# LightsPCB.net
KiCad netlist of a schematic drawn in EAGLE
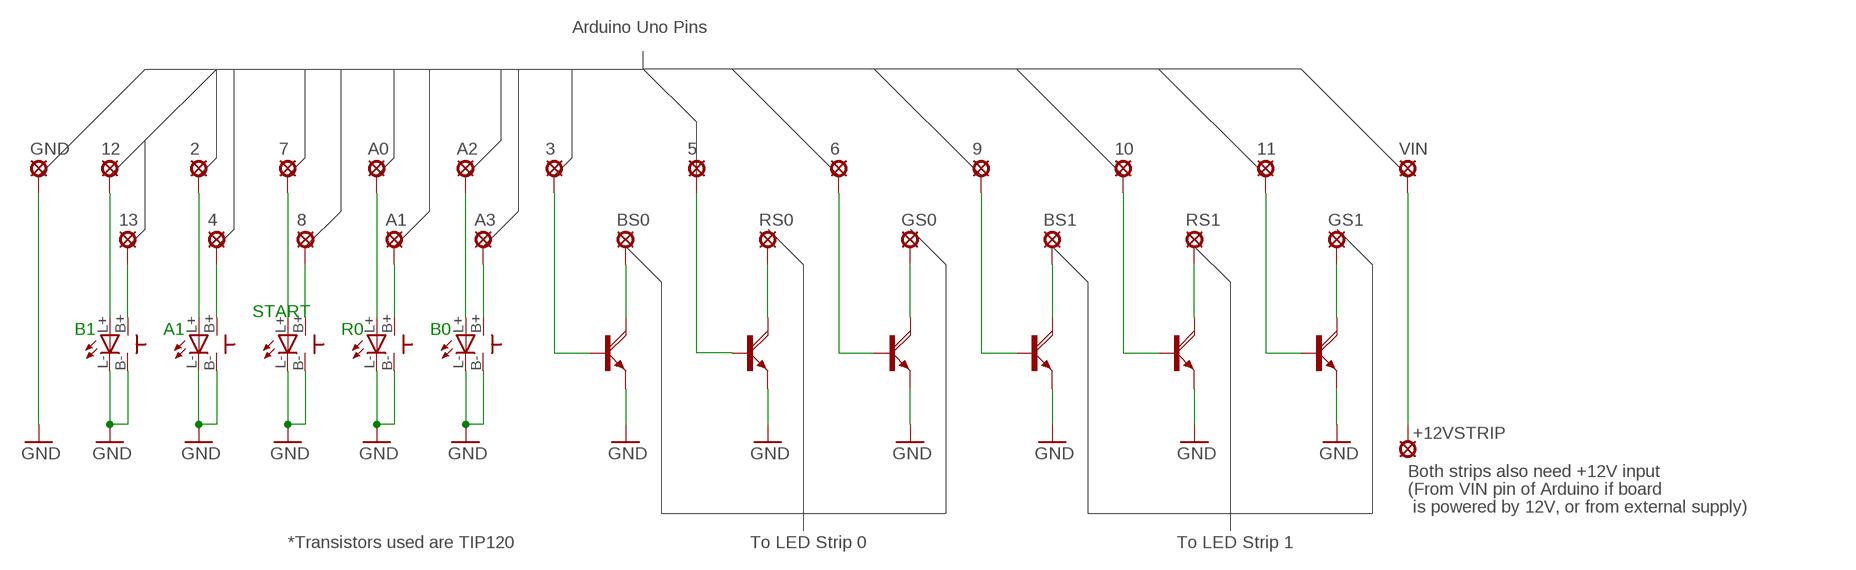
[diagram p0: schematic, sheet 1]

(export (version "E")
  (design (tool "Eeschema 10.0.6"))
  (components
    (comp (ref "+12VSTRIP")
      (value "LSP10")
      (footprint "eagle-import:LSP10")
      (libsource (lib "eagle-import") (part "LSP10"))
    )
    (comp (ref "2")
      (value "LSP10")
      (footprint "eagle-import:LSP10")
      (libsource (lib "eagle-import") (part "LSP10"))
    )
    (comp (ref "3")
      (value "LSP10")
      (footprint "eagle-import:LSP10")
      (libsource (lib "eagle-import") (part "LSP10"))
    )
    (comp (ref "4")
      (value "LSP10")
      (footprint "eagle-import:LSP10")
      (libsource (lib "eagle-import") (part "LSP10"))
    )
    (comp (ref "5")
      (value "LSP10")
      (footprint "eagle-import:LSP10")
      (libsource (lib "eagle-import") (part "LSP10"))
    )
    (comp (ref "6")
      (value "LSP10")
      (footprint "eagle-import:LSP10")
      (libsource (lib "eagle-import") (part "LSP10"))
    )
    (comp (ref "7")
      (value "LSP10")
      (footprint "eagle-import:LSP10")
      (libsource (lib "eagle-import") (part "LSP10"))
    )
    (comp (ref "8")
      (value "LSP10")
      (footprint "eagle-import:LSP10")
      (libsource (lib "eagle-import") (part "LSP10"))
    )
    (comp (ref "9")
      (value "LSP10")
      (footprint "eagle-import:LSP10")
      (libsource (lib "eagle-import") (part "LSP10"))
    )
    (comp (ref "10")
      (value "LSP10")
      (footprint "eagle-import:LSP10")
      (libsource (lib "eagle-import") (part "LSP10"))
    )
    (comp (ref "11")
      (value "LSP10")
      (footprint "eagle-import:LSP10")
      (libsource (lib "eagle-import") (part "LSP10"))
    )
    (comp (ref "12")
      (value "LSP10")
      (footprint "eagle-import:LSP10")
      (libsource (lib "eagle-import") (part "LSP10"))
    )
    (comp (ref "13")
      (value "LSP10")
      (footprint "eagle-import:LSP10")
      (libsource (lib "eagle-import") (part "LSP10"))
    )
    (comp (ref "A0")
      (value "LSP10")
      (footprint "eagle-import:LSP10")
      (libsource (lib "eagle-import") (part "LSP10"))
    )
    (comp (ref "A1")
      (value "LSP10")
      (footprint "eagle-import:LSP10")
      (libsource (lib "eagle-import") (part "LSP10"))
    )
    (comp (ref "A2")
      (value "LSP10")
      (footprint "eagle-import:LSP10")
      (libsource (lib "eagle-import") (part "LSP10"))
    )
    (comp (ref "A3")
      (value "LSP10")
      (footprint "eagle-import:LSP10")
      (libsource (lib "eagle-import") (part "LSP10"))
    )
    (comp (ref "B0")
      (value "LEDBUTTON")
      (footprint "eagle-import:LEDBUTTON")
      (libsource (lib "eagle-import") (part "LEDBUTTON"))
    )
    (comp (ref "B1")
      (value "LEDBUTTON")
      (footprint "eagle-import:LEDBUTTON")
      (libsource (lib "eagle-import") (part "LEDBUTTON"))
    )
    (comp (ref "BS0")
      (value "LSP10")
      (footprint "eagle-import:LSP10")
      (libsource (lib "eagle-import") (part "LSP10"))
    )
    (comp (ref "BS1")
      (value "LSP10")
      (footprint "eagle-import:LSP10")
      (libsource (lib "eagle-import") (part "LSP10"))
    )
    (comp (ref "GND")
      (value "LSP10")
      (footprint "eagle-import:LSP10")
      (libsource (lib "eagle-import") (part "LSP10"))
    )
    (comp (ref "GS0")
      (value "LSP10")
      (footprint "eagle-import:LSP10")
      (libsource (lib "eagle-import") (part "LSP10"))
    )
    (comp (ref "GS1")
      (value "LSP10")
      (footprint "eagle-import:LSP10")
      (libsource (lib "eagle-import") (part "LSP10"))
    )
    (comp (ref "R0")
      (value "LEDBUTTON")
      (footprint "eagle-import:LEDBUTTON")
      (libsource (lib "eagle-import") (part "LEDBUTTON"))
    )
    (comp (ref "R1")
      (value "LEDBUTTON")
      (footprint "eagle-import:LEDBUTTON")
      (libsource (lib "eagle-import") (part "LEDBUTTON"))
    )
    (comp (ref "RS0")
      (value "LSP10")
      (footprint "eagle-import:LSP10")
      (libsource (lib "eagle-import") (part "LSP10"))
    )
    (comp (ref "RS1")
      (value "LSP10")
      (footprint "eagle-import:LSP10")
      (libsource (lib "eagle-import") (part "LSP10"))
    )
    (comp (ref "START")
      (value "LEDBUTTON")
      (footprint "eagle-import:LEDBUTTON")
      (libsource (lib "eagle-import") (part "LEDBUTTON"))
    )
    (comp (ref "U1")
      (value "TIP120")
      (footprint "eagle-import:TO220AH")
      (libsource (lib "eagle-import") (part "TIP120"))
    )
    (comp (ref "U2")
      (value "TIP120")
      (footprint "eagle-import:TO220AH")
      (libsource (lib "eagle-import") (part "TIP120"))
    )
    (comp (ref "U3")
      (value "TIP120")
      (footprint "eagle-import:TO220AH")
      (libsource (lib "eagle-import") (part "TIP120"))
    )
    (comp (ref "U4")
      (value "TIP120")
      (footprint "eagle-import:TO220AH")
      (libsource (lib "eagle-import") (part "TIP120"))
    )
    (comp (ref "U5")
      (value "TIP120")
      (footprint "eagle-import:TO220AH")
      (libsource (lib "eagle-import") (part "TIP120"))
    )
    (comp (ref "U6")
      (value "TIP120")
      (footprint "eagle-import:TO220AH")
      (libsource (lib "eagle-import") (part "TIP120"))
    )
    (comp (ref "VIN")
      (value "LSP10")
      (footprint "eagle-import:LSP10")
      (libsource (lib "eagle-import") (part "LSP10"))
    )
  )
  (nets
    (net (code "1") (name "GND") (class "Default")
      (node (ref "B0") (pin "B-") (pinfunction "B-_B-") (pintype "bidirectional"))
      (node (ref "B0") (pin "L-") (pinfunction "L-_L-") (pintype "bidirectional"))
      (node (ref "B1") (pin "B-") (pinfunction "B-_B-") (pintype "bidirectional"))
      (node (ref "B1") (pin "L-") (pinfunction "L-_L-") (pintype "bidirectional"))
      (node (ref "GND") (pin "MP") (pinfunction "MP_MP") (pintype "passive"))
      (node (ref "R0") (pin "B-") (pinfunction "B-_B-") (pintype "bidirectional"))
      (node (ref "R0") (pin "L-") (pinfunction "L-_L-") (pintype "bidirectional"))
      (node (ref "R1") (pin "B-") (pinfunction "B-_B-") (pintype "bidirectional"))
      (node (ref "R1") (pin "L-") (pinfunction "L-_L-") (pintype "bidirectional"))
      (node (ref "START") (pin "B-") (pinfunction "B-_B-") (pintype "bidirectional"))
      (node (ref "START") (pin "L-") (pinfunction "L-_L-") (pintype "bidirectional"))
      (node (ref "U1") (pin "E") (pinfunction "E_E") (pintype "passive"))
      (node (ref "U2") (pin "E") (pinfunction "E_E") (pintype "passive"))
      (node (ref "U3") (pin "E") (pinfunction "E_E") (pintype "passive"))
      (node (ref "U4") (pin "E") (pinfunction "E_E") (pintype "passive"))
      (node (ref "U5") (pin "E") (pinfunction "E_E") (pintype "passive"))
      (node (ref "U6") (pin "E") (pinfunction "E_E") (pintype "passive"))
    )
    (net (code "2") (name "Net-(+12VSTRIP-PadMP)") (class "Default")
      (node (ref "+12VSTRIP") (pin "MP") (pinfunction "MP_MP") (pintype "passive"))
      (node (ref "VIN") (pin "MP") (pinfunction "MP_MP") (pintype "passive"))
    )
    (net (code "3") (name "Net-(2-PadMP)") (class "Default")
      (node (ref "2") (pin "MP") (pinfunction "MP_MP") (pintype "passive"))
      (node (ref "R1") (pin "L+") (pinfunction "L+_L+") (pintype "bidirectional"))
    )
    (net (code "4") (name "Net-(3-PadMP)") (class "Default")
      (node (ref "3") (pin "MP") (pinfunction "MP_MP") (pintype "passive"))
      (node (ref "U1") (pin "B") (pinfunction "B_B") (pintype "passive"))
    )
    (net (code "5") (name "Net-(4-PadMP)") (class "Default")
      (node (ref "4") (pin "MP") (pinfunction "MP_MP") (pintype "passive"))
      (node (ref "R1") (pin "B+") (pinfunction "B+_B+") (pintype "bidirectional"))
    )
    (net (code "6") (name "Net-(5-PadMP)") (class "Default")
      (node (ref "5") (pin "MP") (pinfunction "MP_MP") (pintype "passive"))
      (node (ref "U2") (pin "B") (pinfunction "B_B") (pintype "passive"))
    )
    (net (code "7") (name "Net-(6-PadMP)") (class "Default")
      (node (ref "6") (pin "MP") (pinfunction "MP_MP") (pintype "passive"))
      (node (ref "U3") (pin "B") (pinfunction "B_B") (pintype "passive"))
    )
    (net (code "8") (name "Net-(7-PadMP)") (class "Default")
      (node (ref "7") (pin "MP") (pinfunction "MP_MP") (pintype "passive"))
      (node (ref "START") (pin "L+") (pinfunction "L+_L+") (pintype "bidirectional"))
    )
    (net (code "9") (name "Net-(8-PadMP)") (class "Default")
      (node (ref "8") (pin "MP") (pinfunction "MP_MP") (pintype "passive"))
      (node (ref "START") (pin "B+") (pinfunction "B+_B+") (pintype "bidirectional"))
    )
    (net (code "10") (name "Net-(9-PadMP)") (class "Default")
      (node (ref "9") (pin "MP") (pinfunction "MP_MP") (pintype "passive"))
      (node (ref "U5") (pin "B") (pinfunction "B_B") (pintype "passive"))
    )
    (net (code "11") (name "Net-(10-PadMP)") (class "Default")
      (node (ref "10") (pin "MP") (pinfunction "MP_MP") (pintype "passive"))
      (node (ref "U4") (pin "B") (pinfunction "B_B") (pintype "passive"))
    )
    (net (code "12") (name "Net-(11-PadMP)") (class "Default")
      (node (ref "11") (pin "MP") (pinfunction "MP_MP") (pintype "passive"))
      (node (ref "U6") (pin "B") (pinfunction "B_B") (pintype "passive"))
    )
    (net (code "13") (name "Net-(12-PadMP)") (class "Default")
      (node (ref "12") (pin "MP") (pinfunction "MP_MP") (pintype "passive"))
      (node (ref "B1") (pin "L+") (pinfunction "L+_L+") (pintype "bidirectional"))
    )
    (net (code "14") (name "Net-(13-PadMP)") (class "Default")
      (node (ref "13") (pin "MP") (pinfunction "MP_MP") (pintype "passive"))
      (node (ref "B1") (pin "B+") (pinfunction "B+_B+") (pintype "bidirectional"))
    )
    (net (code "15") (name "Net-(A0-PadMP)") (class "Default")
      (node (ref "A0") (pin "MP") (pinfunction "MP_MP") (pintype "passive"))
      (node (ref "R0") (pin "L+") (pinfunction "L+_L+") (pintype "bidirectional"))
    )
    (net (code "16") (name "Net-(A1-PadMP)") (class "Default")
      (node (ref "A1") (pin "MP") (pinfunction "MP_MP") (pintype "passive"))
      (node (ref "R0") (pin "B+") (pinfunction "B+_B+") (pintype "bidirectional"))
    )
    (net (code "17") (name "Net-(A2-PadMP)") (class "Default")
      (node (ref "A2") (pin "MP") (pinfunction "MP_MP") (pintype "passive"))
      (node (ref "B0") (pin "L+") (pinfunction "L+_L+") (pintype "bidirectional"))
    )
    (net (code "18") (name "Net-(A3-PadMP)") (class "Default")
      (node (ref "A3") (pin "MP") (pinfunction "MP_MP") (pintype "passive"))
      (node (ref "B0") (pin "B+") (pinfunction "B+_B+") (pintype "bidirectional"))
    )
    (net (code "19") (name "Net-(BS0-PadMP)") (class "Default")
      (node (ref "BS0") (pin "MP") (pinfunction "MP_MP") (pintype "passive"))
      (node (ref "U1") (pin "C") (pinfunction "C_C") (pintype "passive"))
    )
    (net (code "20") (name "Net-(BS1-PadMP)") (class "Default")
      (node (ref "BS1") (pin "MP") (pinfunction "MP_MP") (pintype "passive"))
      (node (ref "U5") (pin "C") (pinfunction "C_C") (pintype "passive"))
    )
    (net (code "21") (name "Net-(GS0-PadMP)") (class "Default")
      (node (ref "GS0") (pin "MP") (pinfunction "MP_MP") (pintype "passive"))
      (node (ref "U3") (pin "C") (pinfunction "C_C") (pintype "passive"))
    )
    (net (code "22") (name "Net-(GS1-PadMP)") (class "Default")
      (node (ref "GS1") (pin "MP") (pinfunction "MP_MP") (pintype "passive"))
      (node (ref "U6") (pin "C") (pinfunction "C_C") (pintype "passive"))
    )
    (net (code "23") (name "Net-(RS0-PadMP)") (class "Default")
      (node (ref "RS0") (pin "MP") (pinfunction "MP_MP") (pintype "passive"))
      (node (ref "U2") (pin "C") (pinfunction "C_C") (pintype "passive"))
    )
    (net (code "24") (name "Net-(RS1-PadMP)") (class "Default")
      (node (ref "RS1") (pin "MP") (pinfunction "MP_MP") (pintype "passive"))
      (node (ref "U4") (pin "C") (pinfunction "C_C") (pintype "passive"))
    )
  )
)
